# 1_81_Greyscale_OLED_Breakout.net
KiCad netlist of a schematic drawn in EAGLE
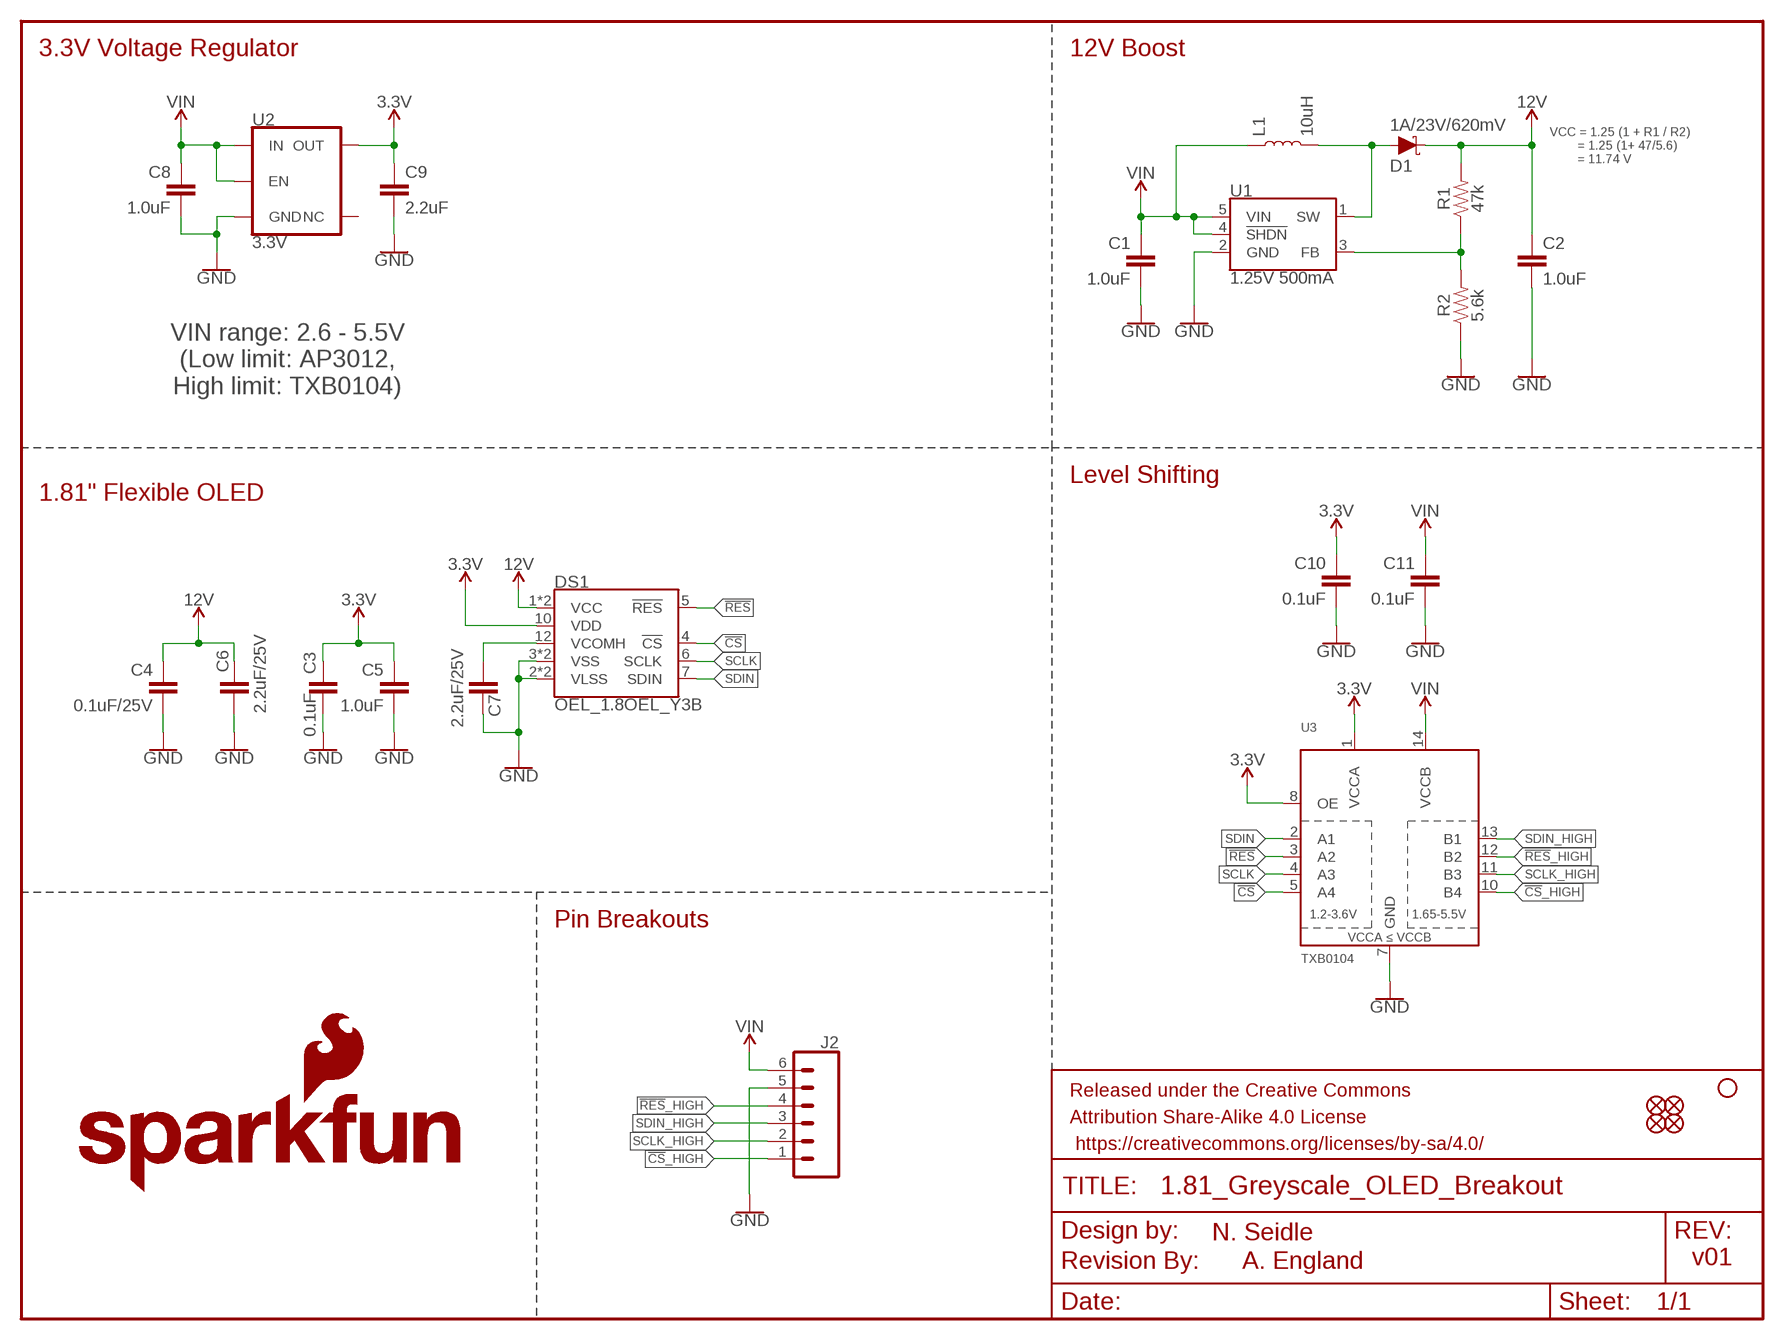
[diagram p0: schematic, sheet 1]

(export (version "E")
  (design (tool "Eeschema 10.0.6"))
  (components
    (comp (ref "C1")
      (value "1.0uF")
      (footprint "eagle-import:0603")
      (libsource (lib "eagle-import") (part "1.0UF-0603-16V-10%"))
    )
    (comp (ref "C2")
      (value "1.0uF")
      (footprint "eagle-import:0805")
      (libsource (lib "eagle-import") (part "1.0UF-0805-25V-10%"))
    )
    (comp (ref "C3")
      (value "0.1uF")
      (footprint "eagle-import:0603")
      (libsource (lib "eagle-import") (part "0.1UF-0603-25V-(+80/-20%)"))
    )
    (comp (ref "C4")
      (value "0.1uF/25V")
      (footprint "eagle-import:0603")
      (libsource (lib "eagle-import") (part "0.1UF-0603-25V-(+80/-20%)"))
    )
    (comp (ref "C5")
      (value "1.0uF")
      (footprint "eagle-import:0603")
      (libsource (lib "eagle-import") (part "1.0UF-0603-16V-10%"))
    )
    (comp (ref "C6")
      (value "2.2uF/25V")
      (footprint "eagle-import:0805")
      (libsource (lib "eagle-import") (part "2.2UF-0805-25V-(+80/-20%)"))
    )
    (comp (ref "C7")
      (value "2.2uF/25V")
      (footprint "eagle-import:0805")
      (libsource (lib "eagle-import") (part "2.2UF-0805-25V-(+80/-20%)"))
    )
    (comp (ref "C8")
      (value "1.0uF")
      (footprint "eagle-import:0603")
      (libsource (lib "eagle-import") (part "1.0UF-0603-16V-10%"))
    )
    (comp (ref "C9")
      (value "2.2uF")
      (footprint "eagle-import:0603")
      (libsource (lib "eagle-import") (part "2.2UF-0603-10V-20%"))
    )
    (comp (ref "C10")
      (value "0.1uF")
      (footprint "eagle-import:0603")
      (libsource (lib "eagle-import") (part "0.1UF-0603-25V-(+80/-20%)"))
    )
    (comp (ref "C11")
      (value "0.1uF")
      (footprint "eagle-import:0603")
      (libsource (lib "eagle-import") (part "0.1UF-0603-25V-(+80/-20%)"))
    )
    (comp (ref "D1")
      (value "1A/23V/620mV")
      (footprint "eagle-import:SOD-323")
      (libsource (lib "eagle-import") (part "DIODE-SCHOTTKY-BAT20J"))
    )
    (comp (ref "DS1")
      (value "OEL_1.8OEL_Y3B")
      (footprint "eagle-import:OEL_1.8_FPC_Y3B")
      (libsource (lib "eagle-import") (part "OEL_1.8OEL_Y3B"))
    )
    (comp (ref "FD1")
      (value "FIDUCIAL1X2")
      (footprint "eagle-import:FIDUCIAL-1X2")
      (libsource (lib "eagle-import") (part "FIDUCIAL1X2"))
    )
    (comp (ref "FD2")
      (value "FIDUCIAL1X2")
      (footprint "eagle-import:FIDUCIAL-1X2")
      (libsource (lib "eagle-import") (part "FIDUCIAL1X2"))
    )
    (comp (ref "FD3")
      (value "FIDUCIAL1X2")
      (footprint "eagle-import:FIDUCIAL-1X2")
      (libsource (lib "eagle-import") (part "FIDUCIAL1X2"))
    )
    (comp (ref "FD4")
      (value "FIDUCIAL1X2")
      (footprint "eagle-import:FIDUCIAL-1X2")
      (libsource (lib "eagle-import") (part "FIDUCIAL1X2"))
    )
    (comp (ref "FRAME1")
      (value "FRAME-LETTER")
      (footprint "eagle-import:CREATIVE_COMMONS")
      (libsource (lib "eagle-import") (part "FRAME-LETTER"))
    )
    (comp (ref "H2")
      (value "STAND-OFF")
      (footprint "eagle-import:STAND-OFF")
      (libsource (lib "eagle-import") (part "STAND-OFF"))
    )
    (comp (ref "J2")
      (value "CONN_06NO_SILK_NO_POP")
      (footprint "eagle-import:1X06_NO_SILK")
      (libsource (lib "eagle-import") (part "CONN_06NO_SILK_NO_POP"))
    )
    (comp (ref "L1")
      (value "10uH")
      (footprint "eagle-import:INDUCTOR_3X3")
      (libsource (lib "eagle-import") (part "INDUCTOR-10UH"))
    )
    (comp (ref "LOGO1")
      (value "SFE_LOGO_NAME_FLAME.1_INCH")
      (footprint "eagle-import:SFE_LOGO_NAME_FLAME_.1")
      (libsource (lib "eagle-import") (part "SFE_LOGO_NAME_FLAME.1_INCH"))
    )
    (comp (ref "LOGO2")
      (value "REVISION")
      (footprint "eagle-import:REVISION")
      (libsource (lib "eagle-import") (part "REVISION"))
    )
    (comp (ref "LOGO3")
      (value "SFE_LOGO_FLAME.1_INCH")
      (footprint "eagle-import:SFE_LOGO_FLAME_.1")
      (libsource (lib "eagle-import") (part "SFE_LOGO_FLAME.1_INCH"))
    )
    (comp (ref "R1")
      (value "47k")
      (footprint "eagle-import:0603")
      (libsource (lib "eagle-import") (part "47KOHM-0603-1/10W-1%"))
    )
    (comp (ref "R2")
      (value "5.6k")
      (footprint "eagle-import:0603")
      (libsource (lib "eagle-import") (part "5.6KOHM-0603-1/10W-1%"))
    )
    (comp (ref "U1")
      (value "1.25V 500mA")
      (footprint "eagle-import:SOT23-5")
      (libsource (lib "eagle-import") (part "AP3012"))
    )
    (comp (ref "U2")
      (value "3.3V")
      (footprint "eagle-import:SOT23-5")
      (libsource (lib "eagle-import") (part "V_REG_AP2112K-3.3V"))
    )
    (comp (ref "U3")
      (value "TXB0104")
      (footprint "eagle-import:SO14")
      (libsource (lib "eagle-import") (part "TXB0104PWRSOIC14"))
    )
  )
  (nets
    (net (code "1") (name "/~{CS}") (class "Default")
      (node (ref "DS1") (pin "4") (pinfunction "~{CS}_4") (pintype "bidirectional"))
      (node (ref "U3") (pin "5") (pinfunction "A4_5") (pintype "bidirectional"))
    )
    (net (code "2") (name "/~{CS}_HIGH") (class "Default")
      (node (ref "J2") (pin "1") (pinfunction "1_1") (pintype "passive"))
      (node (ref "U3") (pin "10") (pinfunction "B4_10") (pintype "bidirectional"))
    )
    (net (code "3") (name "/~{RES}") (class "Default")
      (node (ref "DS1") (pin "5") (pinfunction "~{RES}_5") (pintype "bidirectional"))
      (node (ref "U3") (pin "3") (pinfunction "A2_3") (pintype "bidirectional"))
    )
    (net (code "4") (name "/~{RES}_HIGH") (class "Default")
      (node (ref "J2") (pin "4") (pinfunction "4_4") (pintype "passive"))
      (node (ref "U3") (pin "12") (pinfunction "B2_12") (pintype "bidirectional"))
    )
    (net (code "5") (name "3.3V") (class "Default")
      (node (ref "C10") (pin "1") (pinfunction "1_1") (pintype "passive"))
      (node (ref "C3") (pin "1") (pinfunction "1_1") (pintype "passive"))
      (node (ref "C5") (pin "1") (pinfunction "1_1") (pintype "passive"))
      (node (ref "C9") (pin "1") (pinfunction "1_1") (pintype "passive"))
      (node (ref "DS1") (pin "10") (pinfunction "VDD_10") (pintype "bidirectional"))
      (node (ref "U2") (pin "5") (pinfunction "OUT_5") (pintype "passive"))
      (node (ref "U3") (pin "1") (pinfunction "VCCA_1") (pintype "bidirectional"))
      (node (ref "U3") (pin "8") (pinfunction "OE_8") (pintype "bidirectional"))
    )
    (net (code "6") (name "12V") (class "Default")
      (node (ref "C2") (pin "1") (pinfunction "1_1") (pintype "passive"))
      (node (ref "C4") (pin "1") (pinfunction "1_1") (pintype "passive"))
      (node (ref "C6") (pin "1") (pinfunction "1_1") (pintype "passive"))
      (node (ref "D1") (pin "C") (pinfunction "C_C") (pintype "passive"))
      (node (ref "DS1") (pin "1") (pinfunction "VCC_1") (pintype "bidirectional"))
      (node (ref "DS1") (pin "13") (pinfunction "VCC_13") (pintype "bidirectional"))
      (node (ref "R1") (pin "2") (pinfunction "2_2") (pintype "passive"))
    )
    (net (code "7") (name "GND") (class "Default")
      (node (ref "C1") (pin "2") (pinfunction "2_2") (pintype "passive"))
      (node (ref "C10") (pin "2") (pinfunction "2_2") (pintype "passive"))
      (node (ref "C11") (pin "2") (pinfunction "2_2") (pintype "passive"))
      (node (ref "C2") (pin "2") (pinfunction "2_2") (pintype "passive"))
      (node (ref "C3") (pin "2") (pinfunction "2_2") (pintype "passive"))
      (node (ref "C4") (pin "2") (pinfunction "2_2") (pintype "passive"))
      (node (ref "C5") (pin "2") (pinfunction "2_2") (pintype "passive"))
      (node (ref "C6") (pin "2") (pinfunction "2_2") (pintype "passive"))
      (node (ref "C7") (pin "1") (pinfunction "1_1") (pintype "passive"))
      (node (ref "C8") (pin "2") (pinfunction "2_2") (pintype "passive"))
      (node (ref "C9") (pin "2") (pinfunction "2_2") (pintype "passive"))
      (node (ref "DS1") (pin "2") (pinfunction "VLSS_2") (pintype "bidirectional"))
      (node (ref "DS1") (pin "3") (pinfunction "VSS_3") (pintype "bidirectional"))
      (node (ref "DS1") (pin "8") (pinfunction "VSS_8") (pintype "bidirectional"))
      (node (ref "DS1") (pin "9") (pinfunction "VLSS_9") (pintype "bidirectional"))
      (node (ref "J2") (pin "5") (pinfunction "5_5") (pintype "passive"))
      (node (ref "R2") (pin "1") (pinfunction "1_1") (pintype "passive"))
      (node (ref "U1") (pin "2") (pinfunction "GND_2") (pintype "bidirectional"))
      (node (ref "U2") (pin "2") (pinfunction "GND_2") (pintype "input"))
      (node (ref "U3") (pin "7") (pinfunction "GND_7") (pintype "bidirectional"))
    )
    (net (code "8") (name "Net-(DS1-VCOMH)") (class "Default")
      (node (ref "C7") (pin "2") (pinfunction "2_2") (pintype "passive"))
      (node (ref "DS1") (pin "12") (pinfunction "VCOMH_12") (pintype "bidirectional"))
    )
    (net (code "9") (name "Net-(L1-2)") (class "Default")
      (node (ref "D1") (pin "A") (pinfunction "A_A") (pintype "passive"))
      (node (ref "L1") (pin "P$2") (pinfunction "2_P$2") (pintype "passive"))
      (node (ref "U1") (pin "1") (pinfunction "SW_1") (pintype "bidirectional"))
    )
    (net (code "10") (name "Net-(U1-FB)") (class "Default")
      (node (ref "R1") (pin "1") (pinfunction "1_1") (pintype "passive"))
      (node (ref "R2") (pin "2") (pinfunction "2_2") (pintype "passive"))
      (node (ref "U1") (pin "3") (pinfunction "FB_3") (pintype "bidirectional"))
    )
    (net (code "11") (name "SCLK") (class "Default")
      (node (ref "DS1") (pin "6") (pinfunction "SCLK_6") (pintype "bidirectional"))
      (node (ref "U3") (pin "4") (pinfunction "A3_4") (pintype "bidirectional"))
    )
    (net (code "12") (name "SCLK_HIGH") (class "Default")
      (node (ref "J2") (pin "2") (pinfunction "2_2") (pintype "passive"))
      (node (ref "U3") (pin "11") (pinfunction "B3_11") (pintype "bidirectional"))
    )
    (net (code "13") (name "SDIN") (class "Default")
      (node (ref "DS1") (pin "7") (pinfunction "SDIN_7") (pintype "bidirectional"))
      (node (ref "U3") (pin "2") (pinfunction "A1_2") (pintype "bidirectional"))
    )
    (net (code "14") (name "SDIN_HIGH") (class "Default")
      (node (ref "J2") (pin "3") (pinfunction "3_3") (pintype "passive"))
      (node (ref "U3") (pin "13") (pinfunction "B1_13") (pintype "bidirectional"))
    )
    (net (code "15") (name "VIN") (class "Default")
      (node (ref "C1") (pin "1") (pinfunction "1_1") (pintype "passive"))
      (node (ref "C11") (pin "1") (pinfunction "1_1") (pintype "passive"))
      (node (ref "C8") (pin "1") (pinfunction "1_1") (pintype "passive"))
      (node (ref "J2") (pin "6") (pinfunction "6_6") (pintype "passive"))
      (node (ref "L1") (pin "P$1") (pinfunction "1_P$1") (pintype "passive"))
      (node (ref "U1") (pin "4") (pinfunction "~{SHDN}_4") (pintype "bidirectional"))
      (node (ref "U1") (pin "5") (pinfunction "VIN_5") (pintype "bidirectional"))
      (node (ref "U2") (pin "1") (pinfunction "IN_1") (pintype "input"))
      (node (ref "U2") (pin "3") (pinfunction "EN_3") (pintype "input"))
      (node (ref "U3") (pin "14") (pinfunction "VCCB_14") (pintype "bidirectional"))
    )
    (net (code "16") (name "unconnected-(U2-NC-Pad4)") (class "Default")
      (node (ref "U2") (pin "4") (pinfunction "NC_4") (pintype "no_connect"))
    )
  )
)
